# USB_Interface.net
KiCad netlist of a schematic drawn in Altium Designer
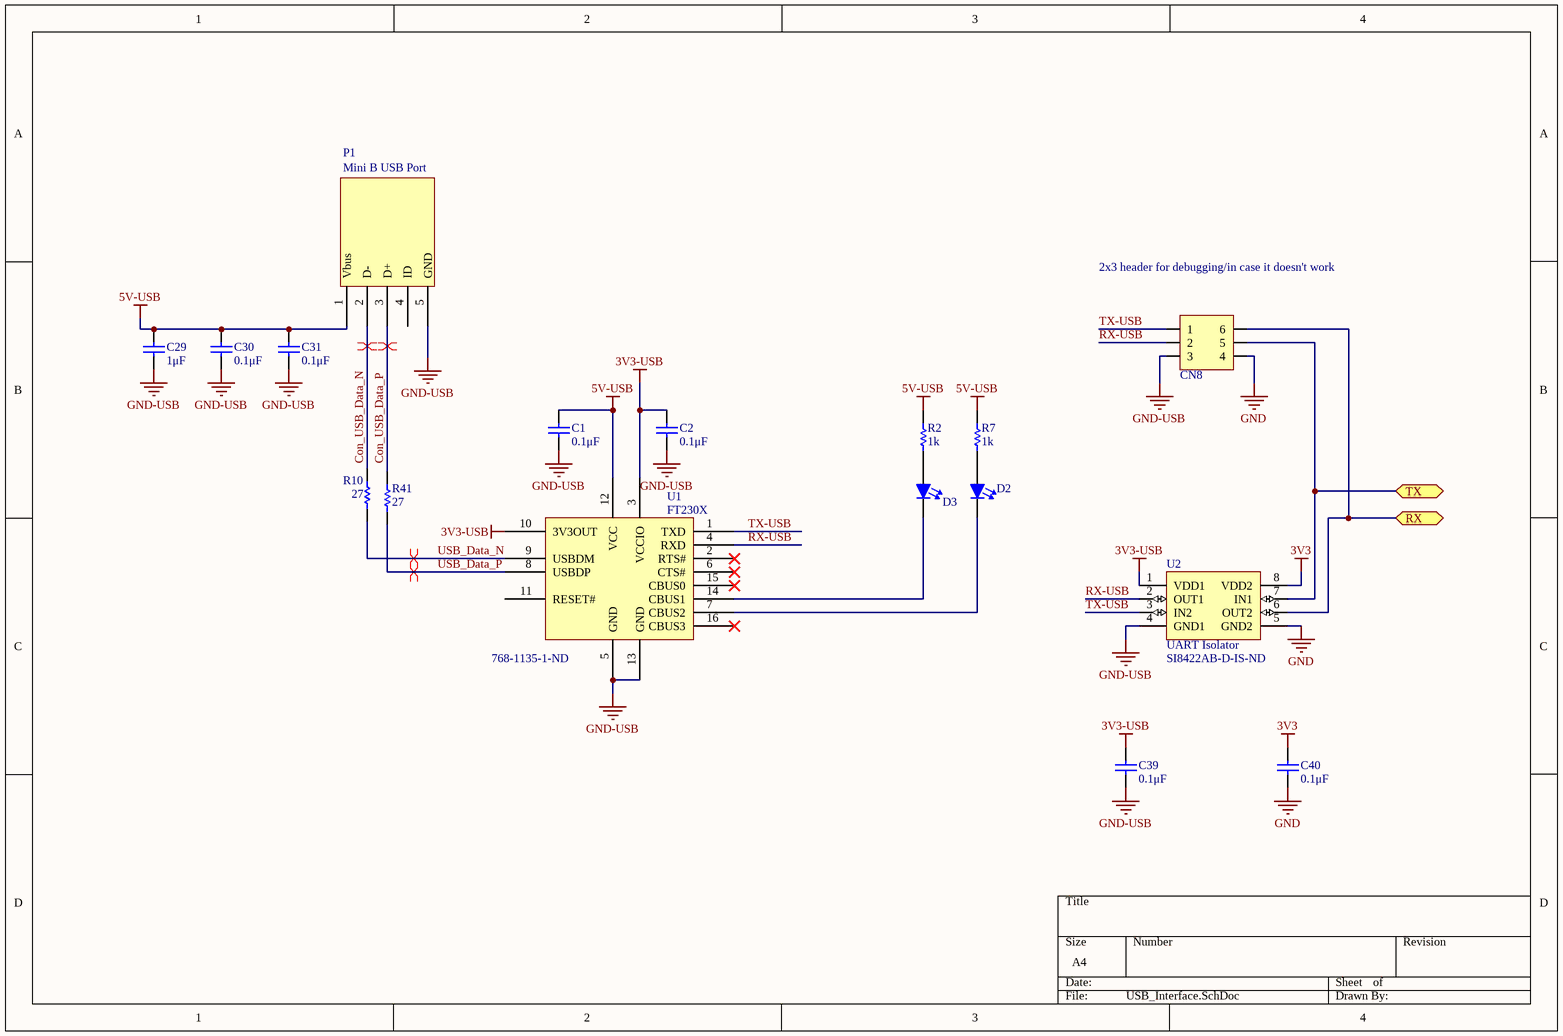
[diagram p0: USB_Interface.SchDoc]

(export (version "E")
  (design (tool "Eeschema 10.0.6"))
  (components
    (comp (ref "C1")
      (value "0.1μF")
      (footprint "CAPC1608N(0603\")")
      (description "Capacitor, Ceramic, 100V, +/- 10%, 0603 SMD, X7R")
      (fields
        (field (name "MFG") "TDK")
        (field (name "PUBLISHER") "AUVic")
        (field (name "CREATED BY") "Ashwin Sira")
      )
      (libsource (lib "AUVic_Integrated_Library_Capacitors") (part "0.1uF 100V 0603 SMD, Ceramic"))
    )
    (comp (ref "C2")
      (value "0.1μF")
      (footprint "CAPC1608N(0603\")")
      (description "Capacitor, Ceramic, 100V, +/- 10%, 0603 SMD, X7R")
      (fields
        (field (name "MFG") "TDK")
        (field (name "PUBLISHER") "AUVic")
        (field (name "CREATED BY") "Ashwin Sira")
      )
      (libsource (lib "AUVic_Integrated_Library_Capacitors") (part "0.1uF 100V 0603 SMD, Ceramic"))
    )
    (comp (ref "C29")
      (value "1μF")
      (footprint "CAPC1608N(0603\")")
      (description "Capacitor, Ceramic, 25V, +/- 10%, 0603 SMD, X5R")
      (fields
        (field (name "MFG") "Murata-Electronics-North-America")
        (field (name "PUBLISHER") "AUVic")
        (field (name "CREATED BY") "Andy Bates")
      )
      (libsource (lib "AUVic_Integrated_Library_Capacitors") (part "1uF 25V 0603 SMD, Ceramic"))
    )
    (comp (ref "C30")
      (value "0.1μF")
      (footprint "CAPC1608N(0603\")")
      (description "Capacitor, Ceramic, 100V, +/- 10%, 0603 SMD, X7R")
      (fields
        (field (name "MFG") "TDK")
        (field (name "PUBLISHER") "AUVic")
        (field (name "CREATED BY") "Ashwin Sira")
      )
      (libsource (lib "AUVic_Integrated_Library_Capacitors") (part "0.1uF 100V 0603 SMD, Ceramic"))
    )
    (comp (ref "C31")
      (value "0.1μF")
      (footprint "CAPC1608N(0603\")")
      (description "Capacitor, Ceramic, 100V, +/- 10%, 0603 SMD, X7R")
      (fields
        (field (name "MFG") "TDK")
        (field (name "PUBLISHER") "AUVic")
        (field (name "CREATED BY") "Ashwin Sira")
      )
      (libsource (lib "AUVic_Integrated_Library_Capacitors") (part "0.1uF 100V 0603 SMD, Ceramic"))
    )
    (comp (ref "C39")
      (value "0.1μF")
      (footprint "CAPC1608N(0603\")")
      (description "Capacitor, Ceramic, 100V, +/- 10%, 0603 SMD, X7R")
      (fields
        (field (name "MFG") "TDK")
        (field (name "PUBLISHER") "AUVic")
        (field (name "CREATED BY") "Ashwin Sira")
      )
      (libsource (lib "AUVic_Integrated_Library_Capacitors") (part "0.1uF 100V 0603 SMD, Ceramic"))
    )
    (comp (ref "C40")
      (value "0.1μF")
      (footprint "CAPC1608N(0603\")")
      (description "Capacitor, Ceramic, 100V, +/- 10%, 0603 SMD, X7R")
      (fields
        (field (name "MFG") "TDK")
        (field (name "PUBLISHER") "AUVic")
        (field (name "CREATED BY") "Ashwin Sira")
      )
      (libsource (lib "AUVic_Integrated_Library_Capacitors") (part "0.1uF 100V 0603 SMD, Ceramic"))
    )
    (comp (ref "CN8")
      (value "Header, Male, 2x3, Pitch: 0.1\" (2.54mm), THT")
      (footprint "Header, Male, 2x3, Pitch: 0.1\" (2.54mm),THT")
      (fields
        (field (name "PUBLISHER") "AUVic")
        (field (name "REVIEWED BY") "*")
        (field (name "CREATED BY") "Andy Bates")
      )
      (libsource (lib "AUVic_Integrated_Library_Connectors") (part "Header, Male, 2x3, Pitch{colon} 0.1{dblquote} (2.54mm), THT"))
    )
    (comp (ref "D2")
      (value "Red")
      (footprint "LED0805")
      (description "LED, 0805 (2012), Green, Clear")
      (fields (field (name "CREATED BY") "Andy Bates"))
      (libsource (lib "AUVic_Integrated_Library_Diodes") (part "LED, 0805 (2012), Green, Clear"))
    )
    (comp (ref "D3")
      (value "Red")
      (footprint "LED0805")
      (description "LED, 0805 (2012), Red, Clear")
      (fields (field (name "CREATED BY") "Ashwin Sira"))
      (libsource (lib "AUVic_Integrated_Library_Diodes") (part "LED, 0805 (2012), Red, Clear"))
    )
    (comp (ref "P1")
      (value "Mini B USB Port")
      (footprint "Mini B USB Footprint")
      (description "Mini B USB Port - Female")
      (fields (field (name "CREATED BY") "Gabriel Green"))
      (libsource (lib "AUVic_Integrated_Library_Connectors") (part "Mini B USB Port"))
    )
    (comp (ref "R2")
      (value "1k")
      (footprint "RESC1608N(0603\")")
      (description "1kR, 1%, 1/10W , 0603, SMD")
      (fields (field (name "CREATED BY") "Andy Bates") (field (name "PUBLISHER") "AUVic"))
      (libsource (lib "AUVic_Schematic_Library_Resistors") (part "1kR, 1%, 1/10W , 0603, SMD"))
    )
    (comp (ref "R7")
      (value "1k")
      (footprint "RESC1608N(0603\")")
      (description "1kR, 1%, 1/10W , 0603, SMD")
      (fields (field (name "CREATED BY") "Andy Bates") (field (name "PUBLISHER") "AUVic"))
      (libsource (lib "AUVic_Schematic_Library_Resistors") (part "1kR, 1%, 1/10W , 0603, SMD"))
    )
    (comp (ref "R10")
      (value "27")
      (footprint "RESC1608N(0603\")")
      (description "27 Ohm, 1%, 1/10W , 0603, SMD")
      (fields (field (name "CREATED BY") "Andy Bates") (field (name "PUBLISHER") "AUVic"))
      (libsource (lib "AUVic_Integrated_Library_Resistors") (part "27 Ohm, 1%, 1/10W , 0603, SMD"))
    )
    (comp (ref "R41")
      (value "27")
      (footprint "RESC1608N(0603\")")
      (description "27 Ohm, 1%, 1/10W , 0603, SMD")
      (fields (field (name "CREATED BY") "Andy Bates") (field (name "PUBLISHER") "AUVic"))
      (libsource (lib "AUVic_Integrated_Library_Resistors") (part "27 Ohm, 1%, 1/10W , 0603, SMD"))
    )
    (comp (ref "U1")
      (value "FT230X")
      (footprint "SSOP16")
      (fields
        (field (name "SUPPLIER PART NUMBER 1") "768-1135-1-ND")
        (field (name "CREATED BY") "Gabriel Green")
      )
      (libsource (lib "AUVic_Integrated_Library_Interface") (part "FTDI - USB to UART"))
    )
    (comp (ref "U2")
      (value "UART Isolator")
      (footprint "SOIC-SN8_M")
      (description "UART Isolators 1/1 1Mbps")
      (fields
        (field (name "SUPPLIER PART NUMBER 1") "SI8422AB-D-IS-ND")
        (field (name "MADE BY") "Andy Bates")
      )
      (libsource (lib "AUVic_Integrated_Library_Interface") (part "UART Isolators 1Mbps 2.7-5.5V"))
    )
  )
  (nets
    (net (code "1") (name "/Con_USB_Data_N") (class "Default")
      (node (ref "P1") (pin "2") (pinfunction "D-_2") (pintype "passive"))
      (node (ref "R10") (pin "1") (pinfunction "1_1") (pintype "passive"))
    )
    (net (code "2") (name "/Con_USB_Data_P") (class "Default")
      (node (ref "P1") (pin "3") (pinfunction "D+_3") (pintype "passive"))
      (node (ref "R41") (pin "1") (pinfunction "1_1") (pintype "passive"))
    )
    (net (code "3") (name "/RX") (class "Default")
      (node (ref "CN8") (pin "6") (pinfunction "6_6") (pintype "passive"))
      (node (ref "U2") (pin "6") (pinfunction "OUT2_6") (pintype "bidirectional"))
    )
    (net (code "4") (name "/RX-USB") (class "Default")
      (node (ref "CN8") (pin "2") (pinfunction "2_2") (pintype "passive"))
      (node (ref "U1") (pin "4") (pinfunction "RXD_4") (pintype "passive"))
      (node (ref "U2") (pin "2") (pinfunction "OUT1_2") (pintype "bidirectional"))
    )
    (net (code "5") (name "/TX") (class "Default")
      (node (ref "CN8") (pin "5") (pinfunction "5_5") (pintype "passive"))
      (node (ref "U2") (pin "7") (pinfunction "IN1_7") (pintype "bidirectional"))
    )
    (net (code "6") (name "/TX-USB") (class "Default")
      (node (ref "CN8") (pin "1") (pinfunction "1_1") (pintype "passive"))
      (node (ref "U1") (pin "1") (pinfunction "TXD_1") (pintype "passive"))
      (node (ref "U2") (pin "3") (pinfunction "IN2_3") (pintype "bidirectional"))
    )
    (net (code "7") (name "/USB_Data_N") (class "Default")
      (node (ref "R10") (pin "2") (pinfunction "2_2") (pintype "passive"))
      (node (ref "U1") (pin "9") (pinfunction "USBDM_9") (pintype "passive"))
    )
    (net (code "8") (name "/USB_Data_P") (class "Default")
      (node (ref "R41") (pin "2") (pinfunction "2_2") (pintype "passive"))
      (node (ref "U1") (pin "8") (pinfunction "USBDP_8") (pintype "passive"))
    )
    (net (code "9") (name "3V3") (class "Default")
      (node (ref "C40") (pin "2") (pinfunction "Cathode_2") (pintype "passive"))
      (node (ref "U2") (pin "8") (pinfunction "VDD2_8") (pintype "power_in"))
    )
    (net (code "10") (name "3V3-USB") (class "Default")
      (node (ref "C2") (pin "2") (pinfunction "Cathode_2") (pintype "passive"))
      (node (ref "C39") (pin "2") (pinfunction "Cathode_2") (pintype "passive"))
      (node (ref "U1") (pin "10") (pinfunction "3V3OUT_10") (pintype "passive"))
      (node (ref "U1") (pin "3") (pinfunction "VCCIO_3") (pintype "passive"))
      (node (ref "U2") (pin "1") (pinfunction "VDD1_1") (pintype "power_in"))
    )
    (net (code "11") (name "5V-USB") (class "Default")
      (node (ref "C1") (pin "2") (pinfunction "Cathode_2") (pintype "passive"))
      (node (ref "C29") (pin "2") (pinfunction "Cathode_2") (pintype "passive"))
      (node (ref "C30") (pin "2") (pinfunction "Cathode_2") (pintype "passive"))
      (node (ref "C31") (pin "2") (pinfunction "Cathode_2") (pintype "passive"))
      (node (ref "P1") (pin "1") (pinfunction "Vbus_1") (pintype "passive"))
      (node (ref "R2") (pin "2") (pinfunction "2_2") (pintype "passive"))
      (node (ref "R7") (pin "2") (pinfunction "2_2") (pintype "passive"))
      (node (ref "U1") (pin "12") (pinfunction "VCC_12") (pintype "passive"))
    )
    (net (code "12") (name "GND") (class "Default")
      (node (ref "C40") (pin "1") (pinfunction "Anode_1") (pintype "passive"))
      (node (ref "CN8") (pin "4") (pinfunction "4_4") (pintype "passive"))
      (node (ref "U2") (pin "5") (pinfunction "GND2_5") (pintype "power_in"))
    )
    (net (code "13") (name "GND-USB") (class "Default")
      (node (ref "C1") (pin "1") (pinfunction "Anode_1") (pintype "passive"))
      (node (ref "C2") (pin "1") (pinfunction "Anode_1") (pintype "passive"))
      (node (ref "C29") (pin "1") (pinfunction "Anode_1") (pintype "passive"))
      (node (ref "C30") (pin "1") (pinfunction "Anode_1") (pintype "passive"))
      (node (ref "C31") (pin "1") (pinfunction "Anode_1") (pintype "passive"))
      (node (ref "C39") (pin "1") (pinfunction "Anode_1") (pintype "passive"))
      (node (ref "CN8") (pin "3") (pinfunction "3_3") (pintype "passive"))
      (node (ref "P1") (pin "5") (pinfunction "GND_5") (pintype "passive"))
      (node (ref "U1") (pin "13") (pinfunction "GND_13") (pintype "passive"))
      (node (ref "U1") (pin "5") (pinfunction "GND_5") (pintype "passive"))
      (node (ref "U2") (pin "4") (pinfunction "GND1_4") (pintype "power_in"))
    )
    (net (code "14") (name "Net-(D2-Anode)") (class "Default")
      (node (ref "D2") (pin "2") (pinfunction "Anode_2") (pintype "passive"))
      (node (ref "R7") (pin "1") (pinfunction "1_1") (pintype "passive"))
    )
    (net (code "15") (name "Net-(D2-Cathode)") (class "Default")
      (node (ref "D2") (pin "1") (pinfunction "Cathode_1") (pintype "passive"))
      (node (ref "U1") (pin "7") (pinfunction "CBUS2_7") (pintype "passive"))
    )
    (net (code "16") (name "Net-(D3-Anode)") (class "Default")
      (node (ref "D3") (pin "2") (pinfunction "Anode_2") (pintype "passive"))
      (node (ref "R2") (pin "1") (pinfunction "1_1") (pintype "passive"))
    )
    (net (code "17") (name "Net-(D3-Cathode)") (class "Default")
      (node (ref "D3") (pin "1") (pinfunction "Cathode_1") (pintype "passive"))
      (node (ref "U1") (pin "14") (pinfunction "CBUS1_14") (pintype "passive"))
    )
    (net (code "18") (name "unconnected-(P1-ID-Pad4)") (class "Default")
      (node (ref "P1") (pin "4") (pinfunction "ID_4") (pintype "passive"))
    )
    (net (code "19") (name "unconnected-(U1-CBUS0-Pad15)") (class "Default")
      (node (ref "U1") (pin "15") (pinfunction "CBUS0_15") (pintype "passive+no_connect"))
    )
    (net (code "20") (name "unconnected-(U1-CBUS3-Pad16)") (class "Default")
      (node (ref "U1") (pin "16") (pinfunction "CBUS3_16") (pintype "passive+no_connect"))
    )
    (net (code "21") (name "unconnected-(U1-CTS#-Pad6)") (class "Default")
      (node (ref "U1") (pin "6") (pinfunction "CTS#_6") (pintype "passive+no_connect"))
    )
    (net (code "22") (name "unconnected-(U1-RESET#-Pad11)") (class "Default")
      (node (ref "U1") (pin "11") (pinfunction "RESET#_11") (pintype "passive"))
    )
    (net (code "23") (name "unconnected-(U1-RTS#-Pad2)") (class "Default")
      (node (ref "U1") (pin "2") (pinfunction "RTS#_2") (pintype "passive+no_connect"))
    )
  )
)
